# neopixel_cab_lights.net
KiCad netlist of a schematic drawn in EAGLE
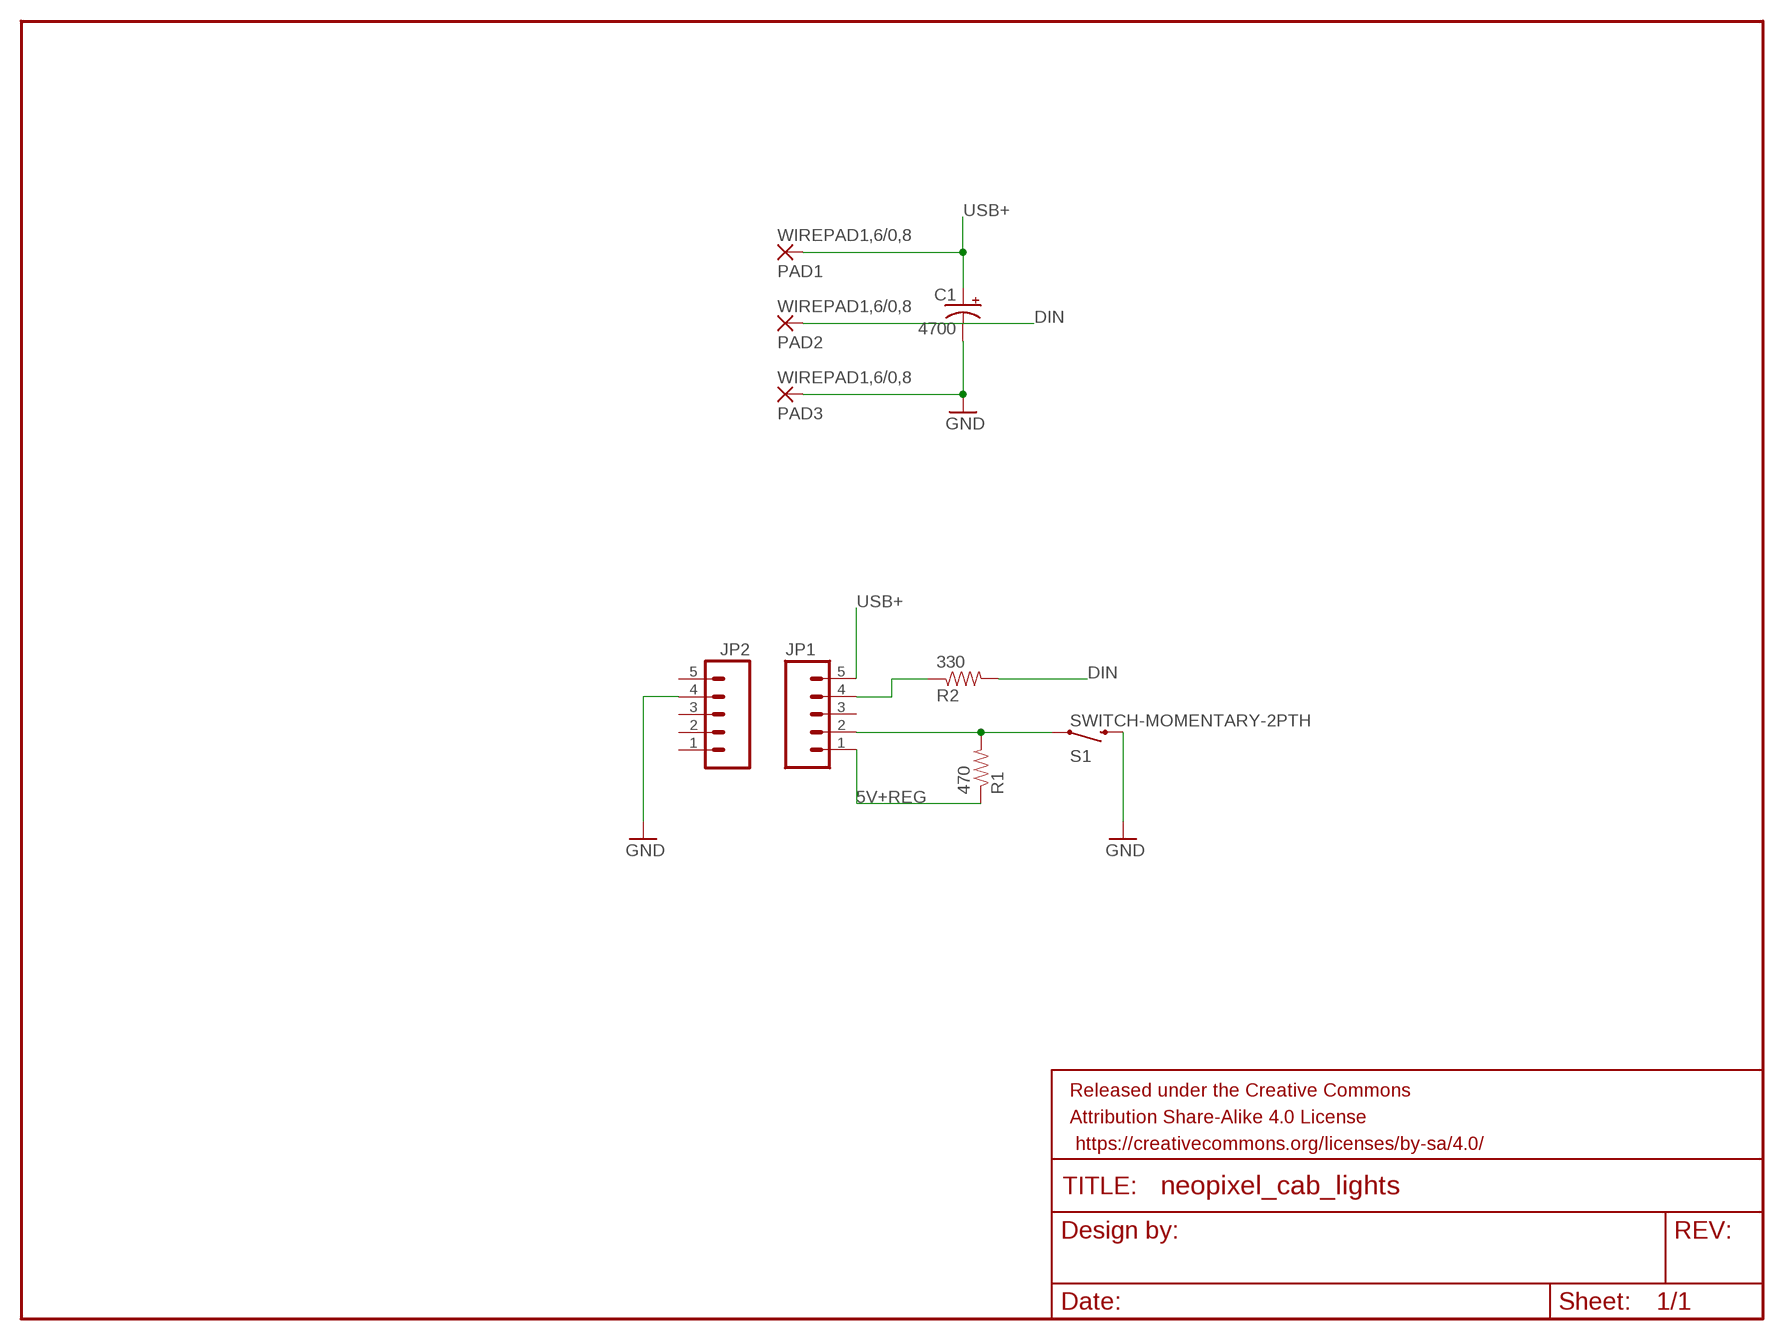
[diagram p0: schematic, sheet 1]

(export (version "E")
  (design (tool "Eeschema 10.0.6"))
  (components
    (comp (ref "C1")
      (value "4700")
      (footprint "eagle-import:CPOL-RADIAL-100UF-25V")
      (libsource (lib "eagle-import") (part "CAP_POLPTH1"))
    )
    (comp (ref "FRAME1")
      (value "FRAME-LETTERNO_PACKAGE")
      (footprint "eagle-import:DUMMY")
      (fields (field (name "DESIGNER") "Nobody"))
      (libsource (lib "eagle-import") (part "FRAME-LETTERNO_PACKAGE"))
    )
    (comp (ref "JP1")
      (value "M05PTH")
      (footprint "eagle-import:1X05")
      (libsource (lib "eagle-import") (part "M05PTH"))
    )
    (comp (ref "JP2")
      (value "M05PTH")
      (footprint "eagle-import:1X05")
      (libsource (lib "eagle-import") (part "M05PTH"))
    )
    (comp (ref "PAD1")
      (value "WIREPAD1,6/0,8")
      (footprint "eagle-import:1,6_0,8")
      (libsource (lib "eagle-import") (part "WIREPAD1,6/0,8"))
    )
    (comp (ref "PAD2")
      (value "WIREPAD1,6/0,8")
      (footprint "eagle-import:1,6_0,8")
      (libsource (lib "eagle-import") (part "WIREPAD1,6/0,8"))
    )
    (comp (ref "PAD3")
      (value "WIREPAD1,6/0,8")
      (footprint "eagle-import:1,6_0,8")
      (libsource (lib "eagle-import") (part "WIREPAD1,6/0,8"))
    )
    (comp (ref "R1")
      (value "470")
      (footprint "eagle-import:AXIAL-0.4")
      (libsource (lib "eagle-import") (part "RESISTORPTH-1/4W"))
    )
    (comp (ref "R2")
      (value "330")
      (footprint "eagle-import:AXIAL-0.4")
      (libsource (lib "eagle-import") (part "RESISTORPTH-1/4W"))
    )
    (comp (ref "S1")
      (value "SWITCH-MOMENTARY-2PTH")
      (footprint "eagle-import:TACTILE-PTH")
      (libsource (lib "eagle-import") (part "SWITCH-MOMENTARY-2PTH"))
    )
  )
  (nets
    (net (code "1") (name "/5V+REG") (class "Default")
      (node (ref "JP1") (pin "1") (pinfunction "1_1") (pintype "passive"))
      (node (ref "R1") (pin "P$1") (pinfunction "1_P$1") (pintype "passive"))
    )
    (net (code "2") (name "/DIN") (class "Default")
      (node (ref "PAD2") (pin "1") (pinfunction "P_1") (pintype "passive"))
      (node (ref "R2") (pin "P$2") (pinfunction "2_P$2") (pintype "passive"))
    )
    (net (code "3") (name "/USB+") (class "Default")
      (node (ref "C1") (pin "1") (pinfunction "+_1") (pintype "passive"))
      (node (ref "JP1") (pin "5") (pinfunction "5_5") (pintype "passive"))
      (node (ref "PAD1") (pin "1") (pinfunction "P_1") (pintype "passive"))
    )
    (net (code "4") (name "GND") (class "Default")
      (node (ref "C1") (pin "2") (pinfunction "-_2") (pintype "passive"))
      (node (ref "JP2") (pin "4") (pinfunction "4_4") (pintype "passive"))
      (node (ref "PAD3") (pin "1") (pinfunction "P_1") (pintype "passive"))
      (node (ref "S1") (pin "3") (pinfunction "2_3") (pintype "passive"))
    )
    (net (code "5") (name "Net-(R1-2)") (class "Default")
      (node (ref "JP1") (pin "2") (pinfunction "2_2") (pintype "passive"))
      (node (ref "R1") (pin "P$2") (pinfunction "2_P$2") (pintype "passive"))
      (node (ref "S1") (pin "1") (pinfunction "1_1") (pintype "passive"))
    )
    (net (code "6") (name "Net-(R2-1)") (class "Default")
      (node (ref "JP1") (pin "4") (pinfunction "4_4") (pintype "passive"))
      (node (ref "R2") (pin "P$1") (pinfunction "1_P$1") (pintype "passive"))
    )
    (net (code "7") (name "unconnected-(JP1-Pad3)") (class "Default")
      (node (ref "JP1") (pin "3") (pinfunction "3_3") (pintype "passive"))
    )
    (net (code "8") (name "unconnected-(JP2-Pad1)") (class "Default")
      (node (ref "JP2") (pin "1") (pinfunction "1_1") (pintype "passive"))
    )
    (net (code "9") (name "unconnected-(JP2-Pad2)") (class "Default")
      (node (ref "JP2") (pin "2") (pinfunction "2_2") (pintype "passive"))
    )
    (net (code "10") (name "unconnected-(JP2-Pad3)") (class "Default")
      (node (ref "JP2") (pin "3") (pinfunction "3_3") (pintype "passive"))
    )
    (net (code "11") (name "unconnected-(JP2-Pad5)") (class "Default")
      (node (ref "JP2") (pin "5") (pinfunction "5_5") (pintype "passive"))
    )
  )
)
